# 02_-IC.net
KiCad netlist of a schematic drawn in Altium Designer
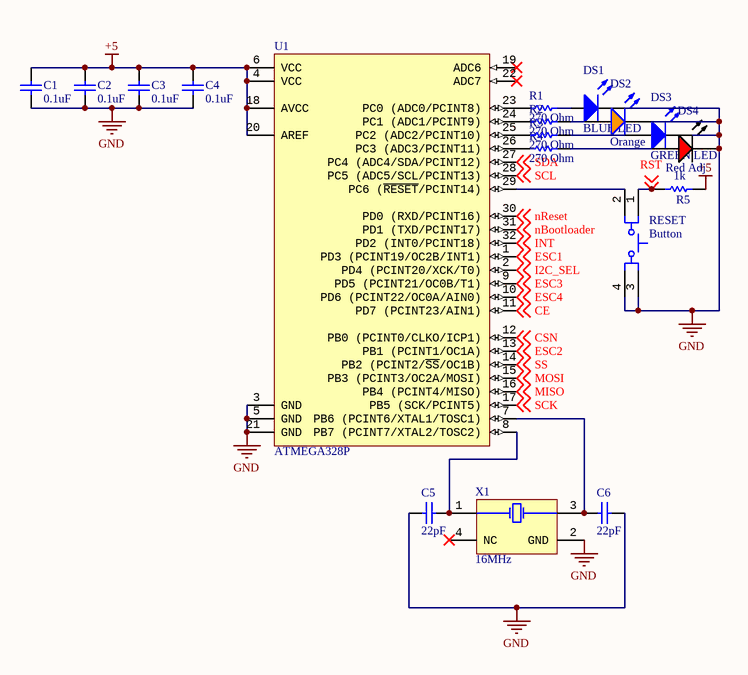
[diagram p0: [02]-IC.SchDoc]

(export (version "E")
  (design (tool "Eeschema 10.0.6"))
  (components
    (comp (ref "C1")
      (value "0.1uF")
      (footprint "CAPC2013X70X50ML10T25")
      (description "Chip Capacitor, 0.1 uF, -20% to 80%, 50 V, -30 to 85 degC, 0805 (2012 Metric), RoHS, Tape and Reel")
      (fields (field (name "MANUFACTURER") "Yageo") (field (name "TOLERANCE") "-20%,+80%"))
      (libsource (lib "Altium Content Vault") (part "CAP-NP-2"))
    )
    (comp (ref "C2")
      (value "0.1uF")
      (footprint "CAPC2013X70X50ML10T25")
      (description "Chip Capacitor, 0.1 uF, -20% to 80%, 50 V, -30 to 85 degC, 0805 (2012 Metric), RoHS, Tape and Reel")
      (fields (field (name "MANUFACTURER") "Yageo") (field (name "TOLERANCE") "-20%,+80%"))
      (libsource (lib "Altium Content Vault") (part "CAP-NP-2"))
    )
    (comp (ref "C3")
      (value "0.1uF")
      (footprint "CAPC2013X70X50ML10T25")
      (description "Chip Capacitor, 0.1 uF, -20% to 80%, 50 V, -30 to 85 degC, 0805 (2012 Metric), RoHS, Tape and Reel")
      (fields (field (name "MANUFACTURER") "Yageo") (field (name "TOLERANCE") "-20%,+80%"))
      (libsource (lib "Altium Content Vault") (part "CAP-NP-2"))
    )
    (comp (ref "C4")
      (value "0.1uF")
      (footprint "CAPC2013X70X50ML10T25")
      (description "Chip Capacitor, 0.1 uF, -20% to 80%, 50 V, -30 to 85 degC, 0805 (2012 Metric), RoHS, Tape and Reel")
      (fields (field (name "MANUFACTURER") "Yageo") (field (name "TOLERANCE") "-20%,+80%"))
      (libsource (lib "Altium Content Vault") (part "CAP-NP-2"))
    )
    (comp (ref "C5")
      (value "22pF")
      (footprint "CAPC1608X90X40ML10T20")
      (description "Chip Capacitor, 22 pF, +/- 5%, 50 V, -55 to 125 degC, 0603 (1608 Metric), RoHS, Tape and Reel")
      (fields (field (name "MPN") "CC0603JRNP09BN220") (field (name "MANUFACTURER") "Yageo"))
      (libsource (lib "") (part "CAP-NP-2_1"))
    )
    (comp (ref "C6")
      (value "22pF")
      (footprint "CAPC1608X90X40ML10T20")
      (description "Chip Capacitor, 22 pF, +/- 5%, 50 V, -55 to 125 degC, 0603 (1608 Metric), RoHS, Tape and Reel")
      (fields (field (name "MPN") "CC0603JRNP09BN220") (field (name "MANUFACTURER") "Yageo"))
      (libsource (lib "") (part "CAP-NP-2_1"))
    )
    (comp (ref "DS1")
      (value "BLUE LED")
      (footprint "0805_A")
      (description "SMD mono-color Chip LED, WL-SMCW, Blue")
      (fields (field (name "MANUFACTURER") "Wuerth Elektronik") (field (name "PARTNUMBER") "150080BS75000"))
      (libsource (lib "Altium Content Vault") (part "WE-LED_K1A2-2"))
    )
    (comp (ref "DS2")
      (value "Orange")
      (footprint "LTST-C171AKT_V")
      (description "LED Uni-Color Orange, 100 mW, 120 mA, -55 to 85 degC, 2-Pin SMD, RoHS, Tape and Reel")
      (fields (field (name "MANUFACTURER") "Lite-On") (field (name "MPN") "LTST-C171AKT"))
      (libsource (lib "Altium Content Vault") (part "LED-ORANGE-AK-2"))
    )
    (comp (ref "DS3")
      (value "GREEN LED")
      (footprint "LITE-ON-LTST-C191KRKT-2_V")
      (description "Chip LED, Green, 574 nm, 40 pF, -55 to 85 degC, 2-Pin SMD, RoHS, Tape and Reel")
      (fields (field (name "MANUFACTURER") "Lite-On") (field (name "MPN") "LTST-C191KGKT"))
      (libsource (lib "Altium Content Vault") (part "LED-AK-2"))
    )
    (comp (ref "DS4")
      (value "Red Adj")
      (footprint "LTST-C170KRKT_V")
      (description "LED Red, 75 mW, 54 mcd, -55 to 85 degC, 2-Pin SMD, RoHS, Tape and Reel")
      (fields (field (name "MANUFACTURER") "Lite-On"))
      (libsource (lib "Altium Content Vault") (part "LED-RED-AK-2"))
    )
    (comp (ref "R1")
      (value "270 Ohm")
      (footprint "RESC2013X50X40NL20T20")
      (description "270 Ohm Resistor")
      (fields (field (name "PART NUMBER") "RR1220P-271-D") (field (name "MANUFACTURER") "Susumu"))
      (libsource (lib "Altium Content Vault") (part "RES"))
    )
    (comp (ref "R2")
      (value "270 Ohm")
      (footprint "RESC2013X50X40NL20T20")
      (description "270 Ohm Resistor")
      (fields (field (name "PART NUMBER") "RR1220P-271-D") (field (name "MANUFACTURER") "Susumu"))
      (libsource (lib "Altium Content Vault") (part "RES"))
    )
    (comp (ref "R3")
      (value "270 Ohm")
      (footprint "RESC2013X50X40NL20T20")
      (description "270 Ohm Resistor")
      (fields (field (name "PART NUMBER") "RR1220P-271-D") (field (name "MANUFACTURER") "Susumu"))
      (libsource (lib "Altium Content Vault") (part "RES"))
    )
    (comp (ref "R4")
      (value "270 Ohm")
      (footprint "RESC2013X50X40NL20T20")
      (description "270 Ohm Resistor")
      (fields (field (name "PART NUMBER") "RR1220P-271-D") (field (name "MANUFACTURER") "Susumu"))
      (libsource (lib "Altium Content Vault") (part "RES"))
    )
    (comp (ref "R5")
      (value "1k")
      (footprint "RESC1005X40X25NL05T10")
      (fields (field (name "MPN") "RC0402FR-071KL") (field (name "MANUFACTURER") "Yageo / Phycomp"))
      (libsource (lib "Altium Content Vault") (part "RES"))
    )
    (comp (ref "RESET")
      (value "Button")
      (footprint "CKCP-PTS645S_V")
      (description "Tact Switch, SPST-NO, 50 mA, -20 to 60 degC, 4-Pin SMD, RoHS, Tape and Reel")
      (fields (field (name "MANUFACTURER") "C&K Components") (field (name "MPN") "PTS645SM43SMTR92 LFS"))
      (libsource (lib "Altium Content Vault") (part "SW-SPST-NO-4"))
    )
    (comp (ref "U1")
      (value "ATMEGA328P")
      (footprint "32A_M")
      (fields (field (name "MPN") "ATmega328P-AU") (field (name "MANUFACTURER") "Microchip Technology"))
      (libsource (lib "Altium Content Vault") (part "MC-8B-ATM48-SQ32"))
    )
    (comp (ref "X1")
      (value "16MHz")
      (footprint "AVX-CX2520DB_V")
      (description "Crystal, 16 MHz, 8 pF, -10 to 70 degC, 4-Pin SMD, RoHS, Tape and Reel")
      (fields (field (name "MANUFACTURER") "AVX") (field (name "TOLERANCE") "15PPM"))
      (libsource (lib "Altium Content Vault") (part "XTAL-1-3-4_A"))
    )
  )
  (nets
    (net (code "1") (name "+5") (class "Default")
      (node (ref "C1") (pin "2") (pinfunction "2_2") (pintype "passive"))
      (node (ref "C2") (pin "2") (pinfunction "2_2") (pintype "passive"))
      (node (ref "C3") (pin "2") (pinfunction "2_2") (pintype "passive"))
      (node (ref "C4") (pin "2") (pinfunction "2_2") (pintype "passive"))
      (node (ref "R5") (pin "1") (pinfunction "1_1") (pintype "passive"))
      (node (ref "U1") (pin "18") (pinfunction "AVCC_18") (pintype "power_in"))
      (node (ref "U1") (pin "20") (pinfunction "AREF_20") (pintype "passive"))
      (node (ref "U1") (pin "4") (pinfunction "VCC_4") (pintype "power_in"))
      (node (ref "U1") (pin "6") (pinfunction "VCC_6") (pintype "power_in"))
    )
    (net (code "2") (name "CE") (class "Default")
      (node (ref "U1") (pin "11") (pinfunction "PD7_(PCINT23/AIN1)_11") (pintype "bidirectional"))
    )
    (net (code "3") (name "CSN") (class "Default")
      (node (ref "U1") (pin "12") (pinfunction "PB0_(PCINT0/CLKO/ICP1)_12") (pintype "bidirectional"))
    )
    (net (code "4") (name "ESC1") (class "Default")
      (node (ref "U1") (pin "1") (pinfunction "PD3_(PCINT19/OC2B/INT1)_1") (pintype "bidirectional"))
    )
    (net (code "5") (name "ESC2") (class "Default")
      (node (ref "U1") (pin "13") (pinfunction "PB1_(PCINT1/OC1A)_13") (pintype "bidirectional"))
    )
    (net (code "6") (name "ESC3") (class "Default")
      (node (ref "U1") (pin "9") (pinfunction "PD5_(PCINT21/OC0B/T1)_9") (pintype "bidirectional"))
    )
    (net (code "7") (name "ESC4") (class "Default")
      (node (ref "U1") (pin "10") (pinfunction "PD6_(PCINT22/OC0A/AIN0)_10") (pintype "bidirectional"))
    )
    (net (code "8") (name "GND") (class "Default")
      (node (ref "C1") (pin "1") (pinfunction "1_1") (pintype "passive"))
      (node (ref "C2") (pin "1") (pinfunction "1_1") (pintype "passive"))
      (node (ref "C3") (pin "1") (pinfunction "1_1") (pintype "passive"))
      (node (ref "C4") (pin "1") (pinfunction "1_1") (pintype "passive"))
      (node (ref "C5") (pin "1") (pinfunction "1_1") (pintype "passive"))
      (node (ref "C6") (pin "2") (pinfunction "2_2") (pintype "passive"))
      (node (ref "DS1") (pin "1") (pinfunction "K_1") (pintype "passive"))
      (node (ref "DS2") (pin "2") (pinfunction "K_2") (pintype "passive"))
      (node (ref "DS3") (pin "2") (pinfunction "K_2") (pintype "passive"))
      (node (ref "DS4") (pin "2") (pinfunction "K_2") (pintype "passive"))
      (node (ref "RESET") (pin "3") (pinfunction "3_3") (pintype "passive"))
      (node (ref "RESET") (pin "4") (pinfunction "4_4") (pintype "passive"))
      (node (ref "U1") (pin "21") (pinfunction "GND_21") (pintype "power_in"))
      (node (ref "U1") (pin "3") (pinfunction "GND_3") (pintype "power_in"))
      (node (ref "U1") (pin "5") (pinfunction "GND_5") (pintype "power_in"))
      (node (ref "X1") (pin "2") (pinfunction "GND_2") (pintype "power_in"))
    )
    (net (code "9") (name "I2C_SEL") (class "Default")
      (node (ref "U1") (pin "2") (pinfunction "PD4_(PCINT20/XCK/T0)_2") (pintype "bidirectional"))
    )
    (net (code "10") (name "INT") (class "Default")
      (node (ref "U1") (pin "32") (pinfunction "PD2_(INT0/PCINT18)_32") (pintype "bidirectional"))
    )
    (net (code "11") (name "MISO") (class "Default")
      (node (ref "U1") (pin "16") (pinfunction "PB4_(PCINT4/MISO)_16") (pintype "bidirectional"))
    )
    (net (code "12") (name "MOSI") (class "Default")
      (node (ref "U1") (pin "15") (pinfunction "PB3_(PCINT3/OC2A/MOSI)_15") (pintype "bidirectional"))
    )
    (net (code "13") (name "Net-(DS1-A)") (class "Default")
      (node (ref "DS1") (pin "2") (pinfunction "A_2") (pintype "passive"))
      (node (ref "R1") (pin "2") (pinfunction "2_2") (pintype "passive"))
    )
    (net (code "14") (name "Net-(DS2-A)") (class "Default")
      (node (ref "DS2") (pin "1") (pinfunction "A_1") (pintype "passive"))
      (node (ref "R2") (pin "2") (pinfunction "2_2") (pintype "passive"))
    )
    (net (code "15") (name "Net-(DS3-A)") (class "Default")
      (node (ref "DS3") (pin "1") (pinfunction "A_1") (pintype "passive"))
      (node (ref "R3") (pin "2") (pinfunction "2_2") (pintype "passive"))
    )
    (net (code "16") (name "Net-(DS4-A)") (class "Default")
      (node (ref "DS4") (pin "1") (pinfunction "A_1") (pintype "passive"))
      (node (ref "R4") (pin "2") (pinfunction "2_2") (pintype "passive"))
    )
    (net (code "17") (name "Net-(U1-PB6_(PCINT6{slash}XTAL1{slash}TOSC1))") (class "Default")
      (node (ref "C6") (pin "1") (pinfunction "1_1") (pintype "passive"))
      (node (ref "U1") (pin "7") (pinfunction "PB6_(PCINT6/XTAL1/TOSC1)_7") (pintype "bidirectional"))
      (node (ref "X1") (pin "3") (pinfunction "HOT_3") (pintype "passive"))
    )
    (net (code "18") (name "Net-(U1-PB7_(PCINT7{slash}XTAL2{slash}TOSC2))") (class "Default")
      (node (ref "C5") (pin "2") (pinfunction "2_2") (pintype "passive"))
      (node (ref "U1") (pin "8") (pinfunction "PB7_(PCINT7/XTAL2/TOSC2)_8") (pintype "bidirectional"))
      (node (ref "X1") (pin "1") (pinfunction "HOT_1") (pintype "passive"))
    )
    (net (code "19") (name "Net-(U1-PC0_(ADC0{slash}PCINT8))") (class "Default")
      (node (ref "R1") (pin "1") (pinfunction "1_1") (pintype "passive"))
      (node (ref "U1") (pin "23") (pinfunction "PC0_(ADC0/PCINT8)_23") (pintype "bidirectional"))
    )
    (net (code "20") (name "Net-(U1-PC1_(ADC1{slash}PCINT9))") (class "Default")
      (node (ref "R2") (pin "1") (pinfunction "1_1") (pintype "passive"))
      (node (ref "U1") (pin "24") (pinfunction "PC1_(ADC1/PCINT9)_24") (pintype "bidirectional"))
    )
    (net (code "21") (name "Net-(U1-PC2_(ADC2{slash}PCINT10))") (class "Default")
      (node (ref "R3") (pin "1") (pinfunction "1_1") (pintype "passive"))
      (node (ref "U1") (pin "25") (pinfunction "PC2_(ADC2/PCINT10)_25") (pintype "bidirectional"))
    )
    (net (code "22") (name "Net-(U1-PC3_(ADC3{slash}PCINT11))") (class "Default")
      (node (ref "R4") (pin "1") (pinfunction "1_1") (pintype "passive"))
      (node (ref "U1") (pin "26") (pinfunction "PC3_(ADC3/PCINT11)_26") (pintype "bidirectional"))
    )
    (net (code "23") (name "Net-(U1-PC6_(~{RESET}{slash}PCINT14))") (class "Default")
      (node (ref "RESET") (pin "2") (pinfunction "2_2") (pintype "passive"))
      (node (ref "U1") (pin "29") (pinfunction "PC6_(~{RESET}/PCINT14)_29") (pintype "bidirectional"))
    )
    (net (code "24") (name "RST") (class "Default")
      (node (ref "R5") (pin "2") (pinfunction "2_2") (pintype "passive"))
      (node (ref "RESET") (pin "1") (pinfunction "1_1") (pintype "passive"))
    )
    (net (code "25") (name "SCK") (class "Default")
      (node (ref "U1") (pin "17") (pinfunction "PB5_(SCK/PCINT5)_17") (pintype "bidirectional"))
    )
    (net (code "26") (name "SCL") (class "Default")
      (node (ref "U1") (pin "28") (pinfunction "PC5_(ADC5/SCL/PCINT13)_28") (pintype "bidirectional"))
    )
    (net (code "27") (name "SDA") (class "Default")
      (node (ref "U1") (pin "27") (pinfunction "PC4_(ADC4/SDA/PCINT12)_27") (pintype "bidirectional"))
    )
    (net (code "28") (name "SS") (class "Default")
      (node (ref "U1") (pin "14") (pinfunction "PB2_(PCINT2/~{SS}/OC1B)_14") (pintype "bidirectional"))
    )
    (net (code "29") (name "nBootloader") (class "Default")
      (node (ref "U1") (pin "31") (pinfunction "PD1_(TXD/PCINT17)_31") (pintype "bidirectional"))
    )
    (net (code "30") (name "nReset") (class "Default")
      (node (ref "U1") (pin "30") (pinfunction "PD0_(RXD/PCINT16)_30") (pintype "bidirectional"))
    )
    (net (code "31") (name "unconnected-(U1-ADC6-Pad19)") (class "Default")
      (node (ref "U1") (pin "19") (pinfunction "ADC6_19") (pintype "input+no_connect"))
    )
    (net (code "32") (name "unconnected-(U1-ADC7-Pad22)") (class "Default")
      (node (ref "U1") (pin "22") (pinfunction "ADC7_22") (pintype "input+no_connect"))
    )
    (net (code "33") (name "unconnected-(X1-NC-Pad4)") (class "Default")
      (node (ref "X1") (pin "4") (pinfunction "NC_4") (pintype "passive+no_connect"))
    )
  )
)
